# SD_CARD.net
KiCad netlist of a schematic drawn in Altium Designer
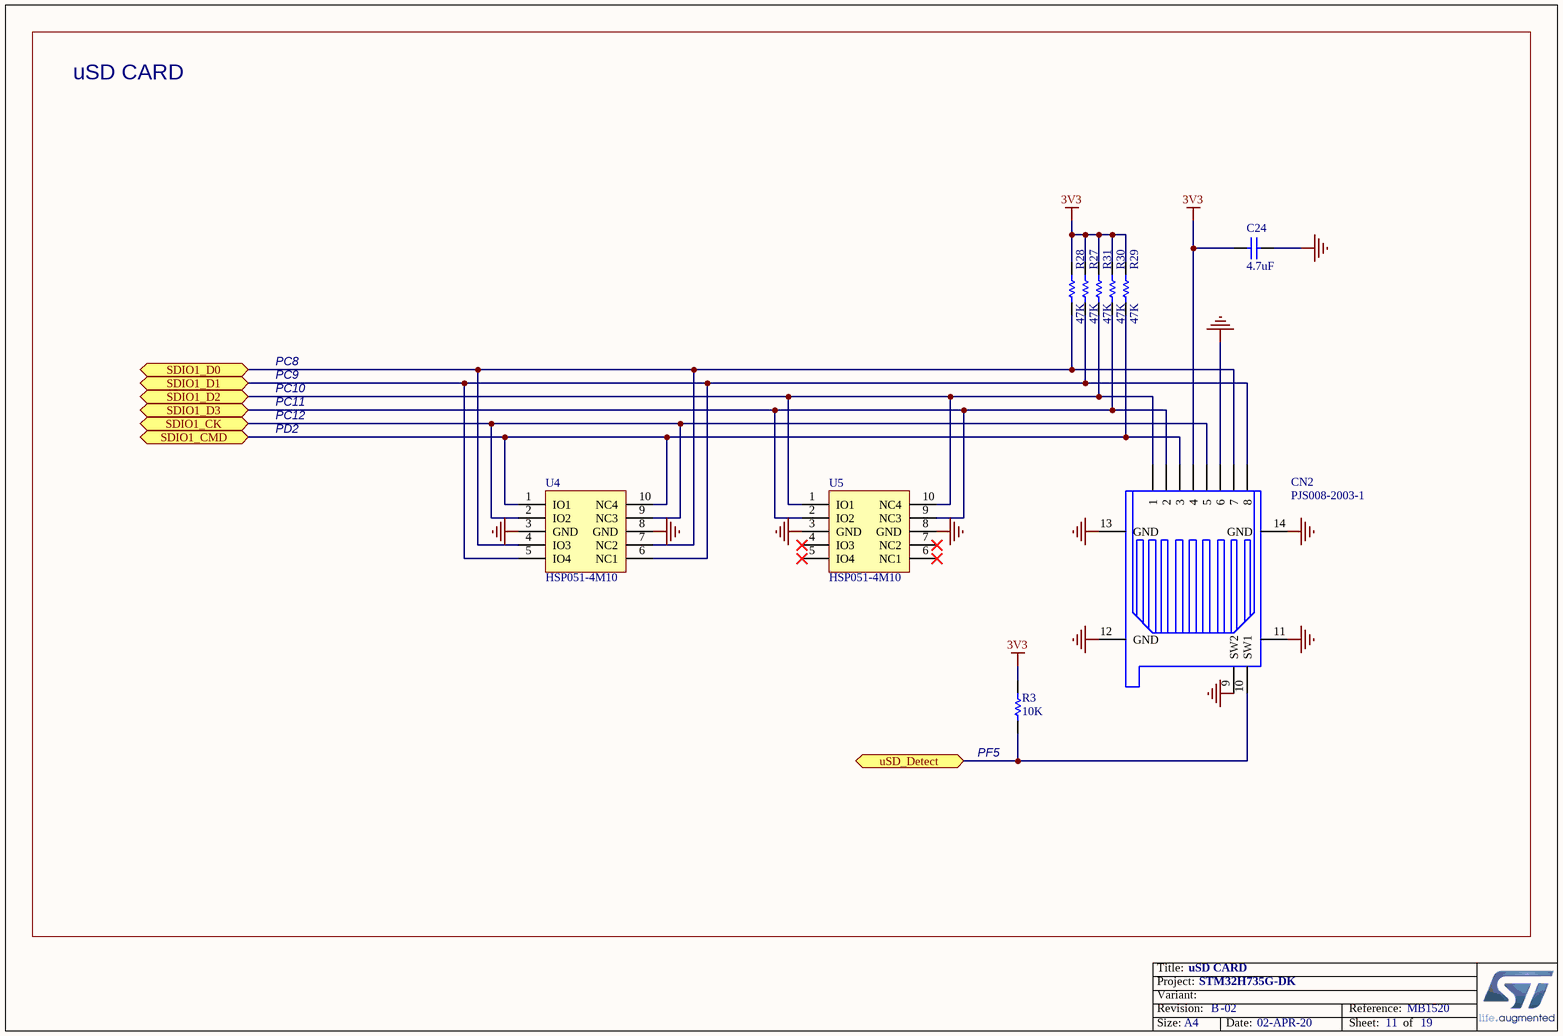
[diagram p0: SD CARD.SchDoc]

(export (version "E")
  (design (tool "Eeschema 10.0.6"))
  (components
    (comp (ref "C24")
      (value "4.7uF")
      (footprint "C0603")
      (description "Capacitor, MLCC, 4.7µF, 10V, X5R, 20%, 0603, T=0,8mm")
      (fields
        (field (name "INTERNAL_PART_NUMBER") "MCD-01121")
        (field (name "MANUFACTURER_PART_NUMBER") "GRM188R61A475ME15")
        (field (name "PROVIDED_BY") "SUBCO")
      )
      (libsource (lib "MCD_PARTS_database") (part "Capacitor"))
    )
    (comp (ref "CN2")
      (value "PJS008-2003-1")
      (footprint "CON_MICROSD_YAMAICHI_PJS008-2003-1")
      (description "MicroSD Card Conn, Reversed-Type, Mnt Push-Push, Positionning holes")
      (fields
        (field (name "INTERNAL_PART_NUMBER") "MCD-00023")
        (field (name "MANUFACTURER") "YAMAICHI")
        (field (name "PROVIDED_BY") "SUBCO")
      )
      (libsource (lib "MCD_PARTS_database") (part "microSD-PJS008-2003"))
    )
    (comp (ref "R3")
      (value "10K")
      (footprint "R0603")
      (description "Resistor,10K,0603,1%,1/10W")
      (fields
        (field (name "INTERNAL_PART_NUMBER") "MCD-00220")
        (field (name "MANUFACTURER_PART_NUMBER") "RC0603FR-0710KL")
        (field (name "PROVIDED_BY") "SUBCO")
      )
      (libsource (lib "MCD_PARTS_database") (part "Resistor"))
    )
    (comp (ref "R27")
      (value "47K")
      (footprint "R0402")
      (description "Resistor,47K,0402,1%,1/16W")
      (fields
        (field (name "INTERNAL_PART_NUMBER") "MCD-00063")
        (field (name "MANUFACTURER_PART_NUMBER") "RC0402FR-0747KL")
        (field (name "PROVIDED_BY") "SUBCO")
      )
      (libsource (lib "MCD_PARTS_database") (part "Resistor"))
    )
    (comp (ref "R28")
      (value "47K")
      (footprint "R0402")
      (description "Resistor,47K,0402,1%,1/16W")
      (fields
        (field (name "INTERNAL_PART_NUMBER") "MCD-00063")
        (field (name "MANUFACTURER_PART_NUMBER") "RC0402FR-0747KL")
        (field (name "PROVIDED_BY") "SUBCO")
      )
      (libsource (lib "MCD_PARTS_database") (part "Resistor"))
    )
    (comp (ref "R29")
      (value "47K")
      (footprint "R0402")
      (description "Resistor,47K,0402,1%,1/16W")
      (fields
        (field (name "INTERNAL_PART_NUMBER") "MCD-00063")
        (field (name "MANUFACTURER_PART_NUMBER") "RC0402FR-0747KL")
        (field (name "PROVIDED_BY") "SUBCO")
      )
      (libsource (lib "MCD_PARTS_database") (part "Resistor"))
    )
    (comp (ref "R30")
      (value "47K")
      (footprint "R0402")
      (description "Resistor,47K,0402,1%,1/16W")
      (fields
        (field (name "INTERNAL_PART_NUMBER") "MCD-00063")
        (field (name "MANUFACTURER_PART_NUMBER") "RC0402FR-0747KL")
        (field (name "PROVIDED_BY") "SUBCO")
      )
      (libsource (lib "MCD_PARTS_database") (part "Resistor"))
    )
    (comp (ref "R31")
      (value "47K")
      (footprint "R0402")
      (description "Resistor,47K,0402,1%,1/16W")
      (fields
        (field (name "INTERNAL_PART_NUMBER") "MCD-00063")
        (field (name "MANUFACTURER_PART_NUMBER") "RC0402FR-0747KL")
        (field (name "PROVIDED_BY") "SUBCO")
      )
      (libsource (lib "MCD_PARTS_database") (part "Resistor"))
    )
    (comp (ref "U4")
      (value "HSP051-4M10")
      (footprint "ESD_UQFN-10L_2P5X1_P050")
      (description "4-line ESD protection for high speed lines")
      (fields
        (field (name "INTERNAL_PART_NUMBER") "MCD-00667")
        (field (name "MANUFACTURER") "STMICROELECTRONICS")
        (field (name "PROVIDED_BY") "SUBCO with ST control")
      )
      (libsource (lib "MCD_PARTS_database") (part "HSP051-4M10"))
    )
    (comp (ref "U5")
      (value "HSP051-4M10")
      (footprint "ESD_UQFN-10L_2P5X1_P050")
      (description "4-line ESD protection for high speed lines")
      (fields
        (field (name "INTERNAL_PART_NUMBER") "MCD-00667")
        (field (name "MANUFACTURER") "STMICROELECTRONICS")
        (field (name "PROVIDED_BY") "SUBCO with ST control")
      )
      (libsource (lib "MCD_PARTS_database") (part "HSP051-4M10"))
    )
  )
  (nets
    (net (code "1") (name "/SDIO1_CK") (class "Default")
      (node (ref "CN2") (pin "5") (pinfunction "5_5") (pintype "passive"))
      (node (ref "U4") (pin "2") (pinfunction "IO2_2") (pintype "passive"))
      (node (ref "U4") (pin "9") (pinfunction "NC3_9") (pintype "passive"))
    )
    (net (code "2") (name "/SDIO1_CMD") (class "Default")
      (node (ref "CN2") (pin "3") (pinfunction "3_3") (pintype "passive"))
      (node (ref "R29") (pin "1") (pinfunction "1_1") (pintype "passive"))
      (node (ref "U4") (pin "1") (pinfunction "IO1_1") (pintype "passive"))
      (node (ref "U4") (pin "10") (pinfunction "NC4_10") (pintype "passive"))
    )
    (net (code "3") (name "/SDIO1_D0") (class "Default")
      (node (ref "CN2") (pin "7") (pinfunction "7_7") (pintype "passive"))
      (node (ref "R28") (pin "1") (pinfunction "1_1") (pintype "passive"))
      (node (ref "U4") (pin "4") (pinfunction "IO3_4") (pintype "passive"))
      (node (ref "U4") (pin "7") (pinfunction "NC2_7") (pintype "passive"))
    )
    (net (code "4") (name "/SDIO1_D1") (class "Default")
      (node (ref "CN2") (pin "8") (pinfunction "8_8") (pintype "passive"))
      (node (ref "R27") (pin "1") (pinfunction "1_1") (pintype "passive"))
      (node (ref "U4") (pin "5") (pinfunction "IO4_5") (pintype "passive"))
      (node (ref "U4") (pin "6") (pinfunction "NC1_6") (pintype "passive"))
    )
    (net (code "5") (name "/SDIO1_D2") (class "Default")
      (node (ref "CN2") (pin "1") (pinfunction "1_1") (pintype "passive"))
      (node (ref "R31") (pin "1") (pinfunction "1_1") (pintype "passive"))
      (node (ref "U5") (pin "1") (pinfunction "IO1_1") (pintype "passive"))
      (node (ref "U5") (pin "10") (pinfunction "NC4_10") (pintype "passive"))
    )
    (net (code "6") (name "/SDIO1_D3") (class "Default")
      (node (ref "CN2") (pin "2") (pinfunction "2_2") (pintype "passive"))
      (node (ref "R30") (pin "1") (pinfunction "1_1") (pintype "passive"))
      (node (ref "U5") (pin "2") (pinfunction "IO2_2") (pintype "passive"))
      (node (ref "U5") (pin "9") (pinfunction "NC3_9") (pintype "passive"))
    )
    (net (code "7") (name "/uSD_Detect") (class "Default")
      (node (ref "CN2") (pin "10") (pinfunction "SW1_10") (pintype "passive"))
      (node (ref "R3") (pin "1") (pinfunction "1_1") (pintype "passive"))
    )
    (net (code "8") (name "3V3") (class "Default")
      (node (ref "C24") (pin "1") (pinfunction "1_1") (pintype "passive"))
      (node (ref "CN2") (pin "4") (pinfunction "4_4") (pintype "passive"))
      (node (ref "R27") (pin "2") (pinfunction "2_2") (pintype "passive"))
      (node (ref "R28") (pin "2") (pinfunction "2_2") (pintype "passive"))
      (node (ref "R29") (pin "2") (pinfunction "2_2") (pintype "passive"))
      (node (ref "R3") (pin "2") (pinfunction "2_2") (pintype "passive"))
      (node (ref "R30") (pin "2") (pinfunction "2_2") (pintype "passive"))
      (node (ref "R31") (pin "2") (pinfunction "2_2") (pintype "passive"))
    )
    (net (code "9") (name "GND") (class "Default")
      (node (ref "C24") (pin "2") (pinfunction "2_2") (pintype "passive"))
      (node (ref "CN2") (pin "11") (pinfunction "GND_11") (pintype "passive"))
      (node (ref "CN2") (pin "12") (pinfunction "GND_12") (pintype "passive"))
      (node (ref "CN2") (pin "13") (pinfunction "GND_13") (pintype "passive"))
      (node (ref "CN2") (pin "14") (pinfunction "GND_14") (pintype "passive"))
      (node (ref "CN2") (pin "6") (pinfunction "6_6") (pintype "passive"))
      (node (ref "CN2") (pin "9") (pinfunction "SW2_9") (pintype "passive"))
      (node (ref "U4") (pin "3") (pinfunction "GND_3") (pintype "passive"))
      (node (ref "U4") (pin "8") (pinfunction "GND_8") (pintype "passive"))
      (node (ref "U5") (pin "3") (pinfunction "GND_3") (pintype "passive"))
      (node (ref "U5") (pin "8") (pinfunction "GND_8") (pintype "passive"))
    )
    (net (code "10") (name "unconnected-(U5-IO3-Pad4)") (class "Default")
      (node (ref "U5") (pin "4") (pinfunction "IO3_4") (pintype "passive+no_connect"))
    )
    (net (code "11") (name "unconnected-(U5-IO4-Pad5)") (class "Default")
      (node (ref "U5") (pin "5") (pinfunction "IO4_5") (pintype "passive+no_connect"))
    )
    (net (code "12") (name "unconnected-(U5-NC1-Pad6)") (class "Default")
      (node (ref "U5") (pin "6") (pinfunction "NC1_6") (pintype "passive+no_connect"))
    )
    (net (code "13") (name "unconnected-(U5-NC2-Pad7)") (class "Default")
      (node (ref "U5") (pin "7") (pinfunction "NC2_7") (pintype "passive+no_connect"))
    )
  )
)
